# tritiled22_5630.net
KiCad netlist of a schematic drawn in EAGLE
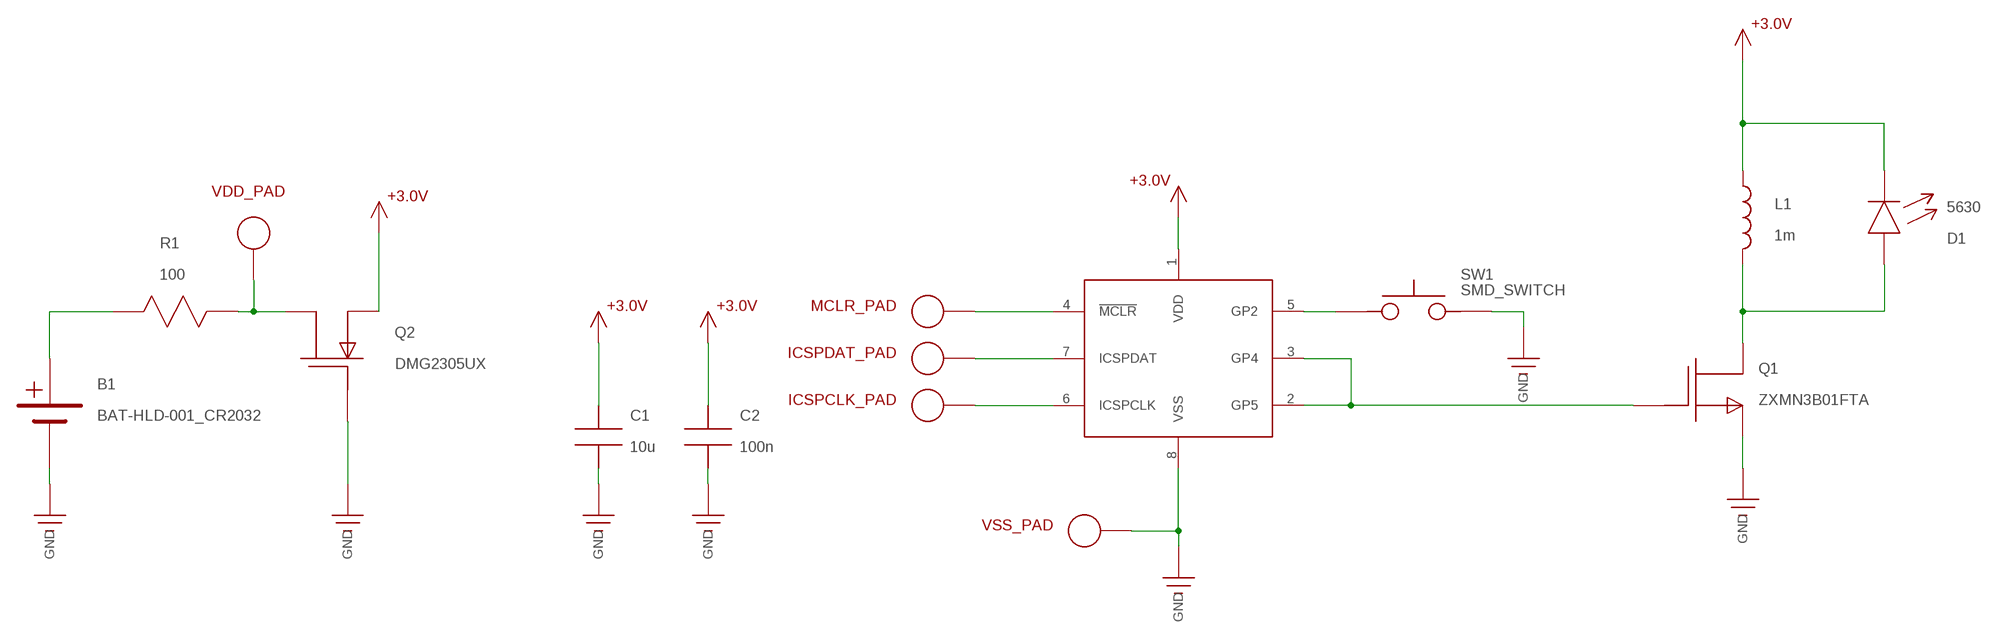
[diagram p0: schematic, sheet 1]

(export (version "E")
  (design (tool "Eeschema 10.0.6"))
  (components
    (comp (ref "B1")
      (value "BAT-HLD-001_CR2032")
      (footprint "eagle-import:CR2032_BAT-HLD_001")
      (libsource (lib "eagle-import") (part "BAT-HLD-001_CR2032"))
    )
    (comp (ref "C1")
      (value "10u")
      (footprint "eagle-import:1206")
      (libsource (lib "eagle-import") (part "C1206"))
    )
    (comp (ref "C2")
      (value "100n")
      (footprint "eagle-import:0805")
      (libsource (lib "eagle-import") (part "C0805"))
    )
    (comp (ref "D1")
      (value "5630")
      (footprint "eagle-import:LED_5630")
      (libsource (lib "eagle-import") (part "LED5630"))
    )
    (comp (ref "ICSPCLK_PAD")
      (value "ICSP_PAD")
      (footprint "eagle-import:ICSP_PAD")
      (libsource (lib "eagle-import") (part "ICSP_PAD"))
    )
    (comp (ref "ICSPDAT_PAD")
      (value "ICSP_PAD")
      (footprint "eagle-import:ICSP_PAD")
      (libsource (lib "eagle-import") (part "ICSP_PAD"))
    )
    (comp (ref "L1")
      (value "1m")
      (footprint "eagle-import:SRR6028_INDUCTOR")
      (libsource (lib "eagle-import") (part "SRR6028_INDUCTOR"))
    )
    (comp (ref "MCLR_PAD")
      (value "ICSP_PAD")
      (footprint "eagle-import:ICSP_PAD")
      (libsource (lib "eagle-import") (part "ICSP_PAD"))
    )
    (comp (ref "Q1")
      (value "ZXMN3B01FTA")
      (footprint "eagle-import:SOT-23")
      (libsource (lib "eagle-import") (part "ZXMN3B01FSOT23"))
    )
    (comp (ref "Q2")
      (value "DMG2305UX")
      (footprint "eagle-import:SOT-23")
      (libsource (lib "eagle-import") (part "DMG2305UXSOT23"))
    )
    (comp (ref "R1")
      (value "100")
      (footprint "eagle-import:R1206")
      (libsource (lib "eagle-import") (part "R1206"))
    )
    (comp (ref "SW1")
      (value "SMD_SWITCH")
      (footprint "eagle-import:SMD_SWITCH")
      (libsource (lib "eagle-import") (part "SMD_SWITCH"))
    )
    (comp (ref "U1")
      (value "PIC12LF1571")
      (footprint "eagle-import:SOIC8")
      (libsource (lib "eagle-import") (part "PIC12LF1571"))
    )
    (comp (ref "VDD_PAD")
      (value "ICSP_PAD")
      (footprint "eagle-import:ICSP_PAD")
      (libsource (lib "eagle-import") (part "ICSP_PAD"))
    )
    (comp (ref "VSS_PAD")
      (value "ICSP_PAD")
      (footprint "eagle-import:ICSP_PAD")
      (libsource (lib "eagle-import") (part "ICSP_PAD"))
    )
  )
  (nets
    (net (code "1") (name "+3.0V") (class "Default")
      (node (ref "C1") (pin "P$1") (pinfunction "P$1_P$1") (pintype "bidirectional"))
      (node (ref "C2") (pin "P$1") (pinfunction "P$1_P$1") (pintype "bidirectional"))
      (node (ref "D1") (pin "C@1") (pinfunction "C_C@1") (pintype "bidirectional"))
      (node (ref "D1") (pin "C@2") (pinfunction "C_C@2") (pintype "bidirectional"))
      (node (ref "L1") (pin "P$1") (pinfunction "1_P$1") (pintype "passive"))
      (node (ref "Q2") (pin "2") (pinfunction "S_2") (pintype "bidirectional"))
      (node (ref "U1") (pin "1") (pinfunction "VDD_1") (pintype "bidirectional"))
    )
    (net (code "2") (name "GND") (class "Default")
      (node (ref "B1") (pin "GND") (pinfunction "0V_GND") (pintype "power_in"))
      (node (ref "C1") (pin "P$2") (pinfunction "P$2_P$2") (pintype "bidirectional"))
      (node (ref "C2") (pin "P$2") (pinfunction "P$2_P$2") (pintype "bidirectional"))
      (node (ref "Q1") (pin "2") (pinfunction "S_2") (pintype "bidirectional"))
      (node (ref "Q2") (pin "1") (pinfunction "G_1") (pintype "bidirectional"))
      (node (ref "SW1") (pin "P$3") (pinfunction "P$2_P$3") (pintype "bidirectional"))
      (node (ref "SW1") (pin "P$4") (pinfunction "P$2_P$4") (pintype "bidirectional"))
      (node (ref "U1") (pin "8") (pinfunction "VSS_8") (pintype "bidirectional"))
      (node (ref "VSS_PAD") (pin "P$2") (pinfunction "P$1_P$2") (pintype "bidirectional"))
    )
    (net (code "3") (name "Net-(B1-+V-Pad+V1)") (class "Default")
      (node (ref "B1") (pin "+V1") (pinfunction "+V_+V1") (pintype "power_in"))
      (node (ref "B1") (pin "+V2") (pinfunction "+V_+V2") (pintype "power_in"))
      (node (ref "R1") (pin "P$1") (pinfunction "P$1_P$1") (pintype "bidirectional"))
    )
    (net (code "4") (name "Net-(ICSPCLK_PAD-P$1)") (class "Default")
      (node (ref "ICSPCLK_PAD") (pin "P$2") (pinfunction "P$1_P$2") (pintype "bidirectional"))
      (node (ref "U1") (pin "6") (pinfunction "ICSPCLK_6") (pintype "bidirectional"))
    )
    (net (code "5") (name "Net-(ICSPDAT_PAD-P$1)") (class "Default")
      (node (ref "ICSPDAT_PAD") (pin "P$2") (pinfunction "P$1_P$2") (pintype "bidirectional"))
      (node (ref "U1") (pin "7") (pinfunction "ICSPDAT_7") (pintype "bidirectional"))
    )
    (net (code "6") (name "Net-(L1-2)") (class "Default")
      (node (ref "D1") (pin "A@1") (pinfunction "A_A@1") (pintype "bidirectional"))
      (node (ref "D1") (pin "A@2") (pinfunction "A_A@2") (pintype "bidirectional"))
      (node (ref "L1") (pin "P$2") (pinfunction "2_P$2") (pintype "passive"))
      (node (ref "Q1") (pin "3") (pinfunction "D_3") (pintype "bidirectional"))
    )
    (net (code "7") (name "Net-(MCLR_PAD-P$1)") (class "Default")
      (node (ref "MCLR_PAD") (pin "P$2") (pinfunction "P$1_P$2") (pintype "bidirectional"))
      (node (ref "U1") (pin "4") (pinfunction "~{MCLR}_4") (pintype "bidirectional"))
    )
    (net (code "8") (name "Net-(Q1-G)") (class "Default")
      (node (ref "Q1") (pin "1") (pinfunction "G_1") (pintype "bidirectional"))
      (node (ref "U1") (pin "2") (pinfunction "GP5_2") (pintype "bidirectional"))
      (node (ref "U1") (pin "3") (pinfunction "GP4_3") (pintype "bidirectional"))
    )
    (net (code "9") (name "Net-(Q2-D)") (class "Default")
      (node (ref "Q2") (pin "3") (pinfunction "D_3") (pintype "bidirectional"))
      (node (ref "R1") (pin "P$2") (pinfunction "P$2_P$2") (pintype "bidirectional"))
      (node (ref "VDD_PAD") (pin "P$2") (pinfunction "P$1_P$2") (pintype "bidirectional"))
    )
    (net (code "10") (name "Net-(U1-GP2)") (class "Default")
      (node (ref "SW1") (pin "P$1") (pinfunction "P$1_P$1") (pintype "bidirectional"))
      (node (ref "SW1") (pin "P$2") (pinfunction "P$1_P$2") (pintype "bidirectional"))
      (node (ref "U1") (pin "5") (pinfunction "GP2_5") (pintype "bidirectional"))
    )
  )
)
